# MDTester.net
KiCad netlist of a schematic drawn in EAGLE
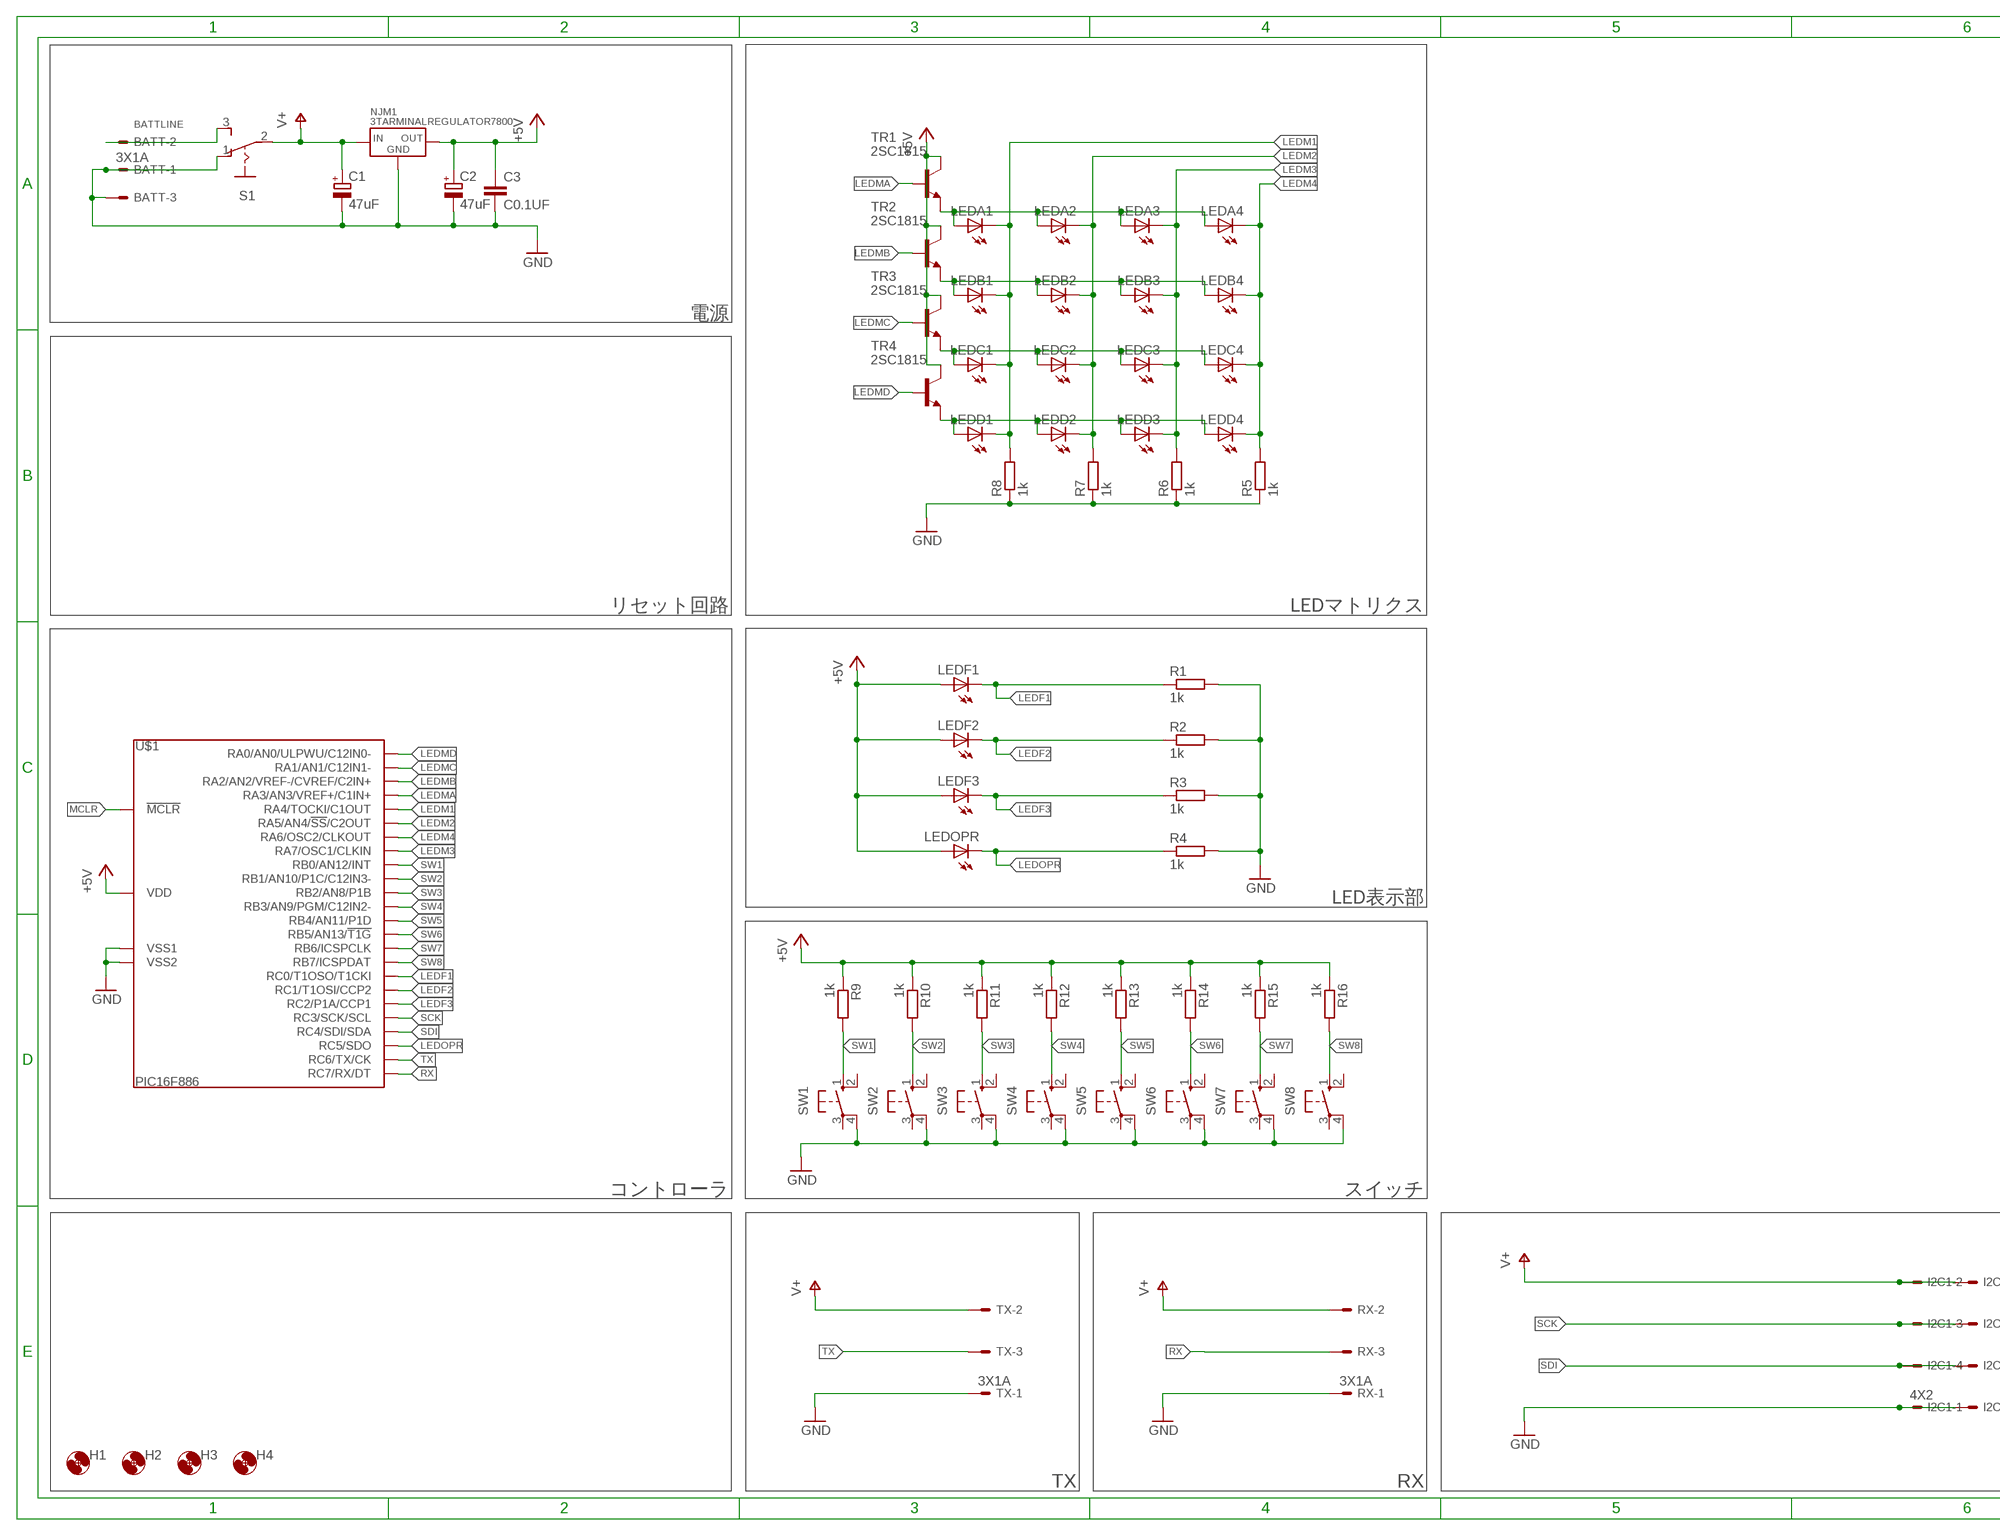
[diagram p0: schematic, sheet 1, part 1 of 2]
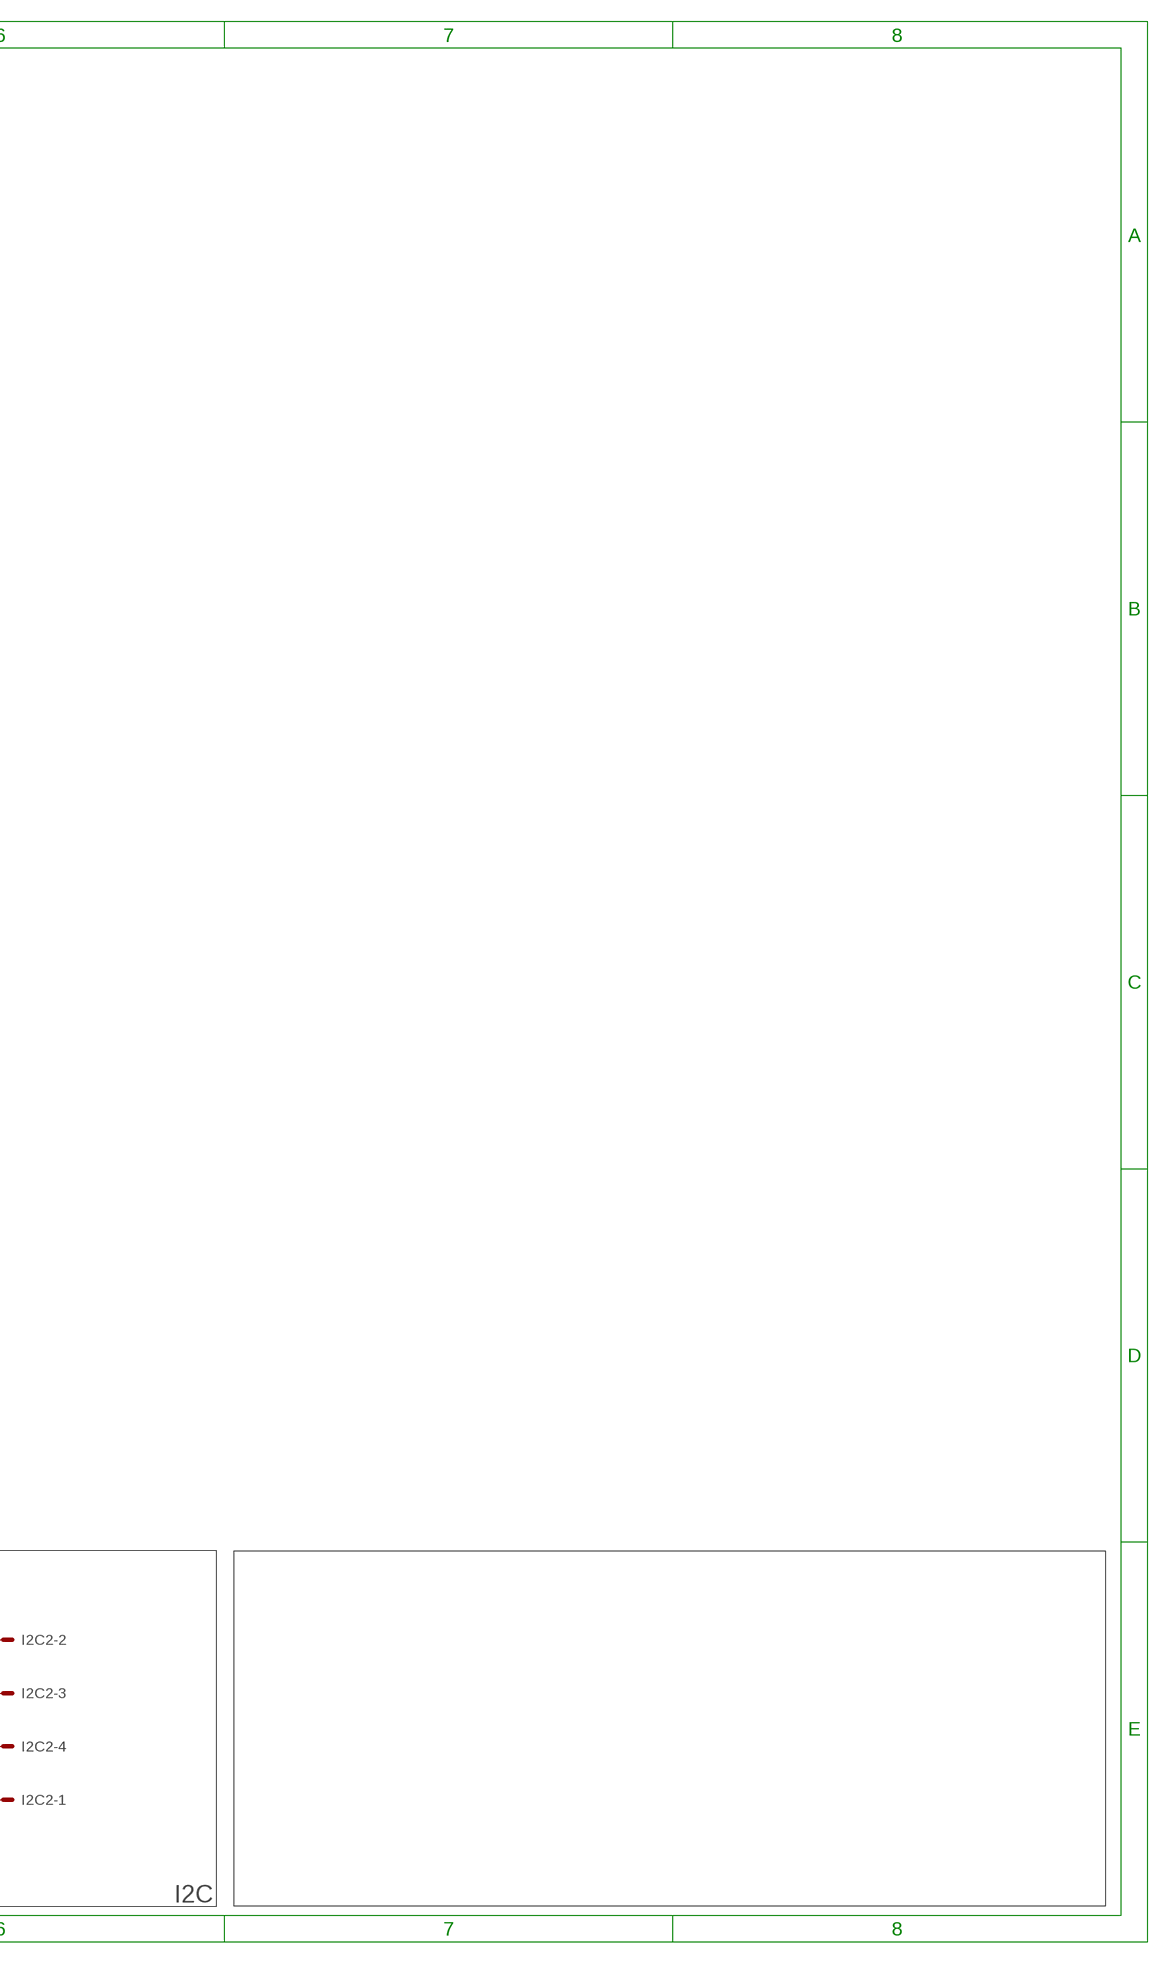
[diagram p1: schematic, sheet 1, part 2 of 2]

(export (version "E")
  (design (tool "Eeschema 10.0.6"))
  (components
    (comp (ref "BATT")
      (value "3X1A")
      (footprint "eagle-import:37203-62A3-003")
      (libsource (lib "eagle-import") (part "3X1A"))
    )
    (comp (ref "C1")
      (value "47uF")
      (footprint "eagle-import:E2-5")
      (libsource (lib "eagle-import") (part "CPOL-EU2-5MM"))
    )
    (comp (ref "C2")
      (value "47uF")
      (footprint "eagle-import:E2-5")
      (libsource (lib "eagle-import") (part "CPOL-EU2-5MM"))
    )
    (comp (ref "C3")
      (value "C0.1UF")
      (footprint "eagle-import:C0.1UF")
      (libsource (lib "eagle-import") (part "C0.1UF"))
    )
    (comp (ref "H1")
      (value "HOLE3.3M3BOLT")
      (footprint "eagle-import:HOLE3.3")
      (libsource (lib "eagle-import") (part "HOLE3.3M3BOLT"))
    )
    (comp (ref "H2")
      (value "HOLE3.3M3BOLT")
      (footprint "eagle-import:HOLE3.3")
      (libsource (lib "eagle-import") (part "HOLE3.3M3BOLT"))
    )
    (comp (ref "H3")
      (value "HOLE3.3M3BOLT")
      (footprint "eagle-import:HOLE3.3")
      (libsource (lib "eagle-import") (part "HOLE3.3M3BOLT"))
    )
    (comp (ref "H4")
      (value "HOLE3.3M3BOLT")
      (footprint "eagle-import:HOLE3.3")
      (libsource (lib "eagle-import") (part "HOLE3.3M3BOLT"))
    )
    (comp (ref "I2C")
      (value "4X2")
      (footprint "eagle-import:37208-62A3-004")
      (libsource (lib "eagle-import") (part "4X2"))
    )
    (comp (ref "LEDA1")
      (value "LED5MM")
      (footprint "eagle-import:LED5MM")
      (libsource (lib "eagle-import") (part "LED5MM"))
    )
    (comp (ref "LEDA2")
      (value "LED5MM")
      (footprint "eagle-import:LED5MM")
      (libsource (lib "eagle-import") (part "LED5MM"))
    )
    (comp (ref "LEDA3")
      (value "LED5MM")
      (footprint "eagle-import:LED5MM")
      (libsource (lib "eagle-import") (part "LED5MM"))
    )
    (comp (ref "LEDA4")
      (value "LED5MM")
      (footprint "eagle-import:LED5MM")
      (libsource (lib "eagle-import") (part "LED5MM"))
    )
    (comp (ref "LEDB1")
      (value "LED5MM")
      (footprint "eagle-import:LED5MM")
      (libsource (lib "eagle-import") (part "LED5MM"))
    )
    (comp (ref "LEDB2")
      (value "LED5MM")
      (footprint "eagle-import:LED5MM")
      (libsource (lib "eagle-import") (part "LED5MM"))
    )
    (comp (ref "LEDB3")
      (value "LED5MM")
      (footprint "eagle-import:LED5MM")
      (libsource (lib "eagle-import") (part "LED5MM"))
    )
    (comp (ref "LEDB4")
      (value "LED5MM")
      (footprint "eagle-import:LED5MM")
      (libsource (lib "eagle-import") (part "LED5MM"))
    )
    (comp (ref "LEDC1")
      (value "LED5MM")
      (footprint "eagle-import:LED5MM")
      (libsource (lib "eagle-import") (part "LED5MM"))
    )
    (comp (ref "LEDC2")
      (value "LED5MM")
      (footprint "eagle-import:LED5MM")
      (libsource (lib "eagle-import") (part "LED5MM"))
    )
    (comp (ref "LEDC3")
      (value "LED5MM")
      (footprint "eagle-import:LED5MM")
      (libsource (lib "eagle-import") (part "LED5MM"))
    )
    (comp (ref "LEDC4")
      (value "LED5MM")
      (footprint "eagle-import:LED5MM")
      (libsource (lib "eagle-import") (part "LED5MM"))
    )
    (comp (ref "LEDD1")
      (value "LED5MM")
      (footprint "eagle-import:LED5MM")
      (libsource (lib "eagle-import") (part "LED5MM"))
    )
    (comp (ref "LEDD2")
      (value "LED5MM")
      (footprint "eagle-import:LED5MM")
      (libsource (lib "eagle-import") (part "LED5MM"))
    )
    (comp (ref "LEDD3")
      (value "LED5MM")
      (footprint "eagle-import:LED5MM")
      (libsource (lib "eagle-import") (part "LED5MM"))
    )
    (comp (ref "LEDD4")
      (value "LED5MM")
      (footprint "eagle-import:LED5MM")
      (libsource (lib "eagle-import") (part "LED5MM"))
    )
    (comp (ref "LEDF1")
      (value "LED5MM")
      (footprint "eagle-import:LED5MM")
      (libsource (lib "eagle-import") (part "LED5MM"))
    )
    (comp (ref "LEDF2")
      (value "LED5MM")
      (footprint "eagle-import:LED5MM")
      (libsource (lib "eagle-import") (part "LED5MM"))
    )
    (comp (ref "LEDF3")
      (value "LED5MM")
      (footprint "eagle-import:LED5MM")
      (libsource (lib "eagle-import") (part "LED5MM"))
    )
    (comp (ref "LEDOPR")
      (value "LED5MM")
      (footprint "eagle-import:LED5MM")
      (libsource (lib "eagle-import") (part "LED5MM"))
    )
    (comp (ref "NJM1")
      (value "3TARMINALREGULATOR7800")
      (footprint "eagle-import:TO-220")
      (libsource (lib "eagle-import") (part "3TARMINALREGULATOR7800"))
    )
    (comp (ref "R1")
      (value "1k")
      (footprint "eagle-import:R3216W")
      (libsource (lib "eagle-import") (part "R-EU_R3216W"))
    )
    (comp (ref "R2")
      (value "1k")
      (footprint "eagle-import:R3216W")
      (libsource (lib "eagle-import") (part "R-EU_R3216W"))
    )
    (comp (ref "R3")
      (value "1k")
      (footprint "eagle-import:R3216W")
      (libsource (lib "eagle-import") (part "R-EU_R3216W"))
    )
    (comp (ref "R4")
      (value "1k")
      (footprint "eagle-import:R3216W")
      (libsource (lib "eagle-import") (part "R-EU_R3216W"))
    )
    (comp (ref "R5")
      (value "1k")
      (footprint "eagle-import:R3216W")
      (libsource (lib "eagle-import") (part "R-EU_R3216W"))
    )
    (comp (ref "R6")
      (value "1k")
      (footprint "eagle-import:R3216W")
      (libsource (lib "eagle-import") (part "R-EU_R3216W"))
    )
    (comp (ref "R7")
      (value "1k")
      (footprint "eagle-import:R3216W")
      (libsource (lib "eagle-import") (part "R-EU_R3216W"))
    )
    (comp (ref "R8")
      (value "1k")
      (footprint "eagle-import:R3216W")
      (libsource (lib "eagle-import") (part "R-EU_R3216W"))
    )
    (comp (ref "R9")
      (value "1k")
      (footprint "eagle-import:R3216W")
      (libsource (lib "eagle-import") (part "R-EU_R3216W"))
    )
    (comp (ref "R10")
      (value "1k")
      (footprint "eagle-import:R3216W")
      (libsource (lib "eagle-import") (part "R-EU_R3216W"))
    )
    (comp (ref "R11")
      (value "1k")
      (footprint "eagle-import:R3216W")
      (libsource (lib "eagle-import") (part "R-EU_R3216W"))
    )
    (comp (ref "R12")
      (value "1k")
      (footprint "eagle-import:R3216W")
      (libsource (lib "eagle-import") (part "R-EU_R3216W"))
    )
    (comp (ref "R13")
      (value "1k")
      (footprint "eagle-import:R3216W")
      (libsource (lib "eagle-import") (part "R-EU_R3216W"))
    )
    (comp (ref "R14")
      (value "1k")
      (footprint "eagle-import:R3216W")
      (libsource (lib "eagle-import") (part "R-EU_R3216W"))
    )
    (comp (ref "R15")
      (value "1k")
      (footprint "eagle-import:R3216W")
      (libsource (lib "eagle-import") (part "R-EU_R3216W"))
    )
    (comp (ref "R16")
      (value "1k")
      (footprint "eagle-import:R3216W")
      (libsource (lib "eagle-import") (part "R-EU_R3216W"))
    )
    (comp (ref "RX")
      (value "3X1A")
      (footprint "eagle-import:37203-62A3-003")
      (libsource (lib "eagle-import") (part "3X1A"))
    )
    (comp (ref "S1")
      (value "SLIDESW")
      (footprint "eagle-import:SLIDESW")
      (libsource (lib "eagle-import") (part "SLIDESW"))
    )
    (comp (ref "SW1")
      (value "TACTSW")
      (footprint "eagle-import:TACT")
      (libsource (lib "eagle-import") (part "TACTSW"))
    )
    (comp (ref "SW2")
      (value "TACTSW")
      (footprint "eagle-import:TACT")
      (libsource (lib "eagle-import") (part "TACTSW"))
    )
    (comp (ref "SW3")
      (value "TACTSW")
      (footprint "eagle-import:TACT")
      (libsource (lib "eagle-import") (part "TACTSW"))
    )
    (comp (ref "SW4")
      (value "TACTSW")
      (footprint "eagle-import:TACT")
      (libsource (lib "eagle-import") (part "TACTSW"))
    )
    (comp (ref "SW5")
      (value "TACTSW")
      (footprint "eagle-import:TACT")
      (libsource (lib "eagle-import") (part "TACTSW"))
    )
    (comp (ref "SW6")
      (value "TACTSW")
      (footprint "eagle-import:TACT")
      (libsource (lib "eagle-import") (part "TACTSW"))
    )
    (comp (ref "SW7")
      (value "TACTSW")
      (footprint "eagle-import:TACT")
      (libsource (lib "eagle-import") (part "TACTSW"))
    )
    (comp (ref "SW8")
      (value "TACTSW")
      (footprint "eagle-import:TACT")
      (libsource (lib "eagle-import") (part "TACTSW"))
    )
    (comp (ref "TR1")
      (value "2SC1815")
      (footprint "eagle-import:TO92-")
      (libsource (lib "eagle-import") (part "2SC1815"))
    )
    (comp (ref "TR2")
      (value "2SC1815")
      (footprint "eagle-import:TO92-")
      (libsource (lib "eagle-import") (part "2SC1815"))
    )
    (comp (ref "TR3")
      (value "2SC1815")
      (footprint "eagle-import:TO92-")
      (libsource (lib "eagle-import") (part "2SC1815"))
    )
    (comp (ref "TR4")
      (value "2SC1815")
      (footprint "eagle-import:TO92-")
      (libsource (lib "eagle-import") (part "2SC1815"))
    )
    (comp (ref "TX")
      (value "3X1A")
      (footprint "eagle-import:37203-62A3-003")
      (libsource (lib "eagle-import") (part "3X1A"))
    )
    (comp (ref "U$1")
      (value "PIC16F886")
      (footprint "eagle-import:DIL28")
      (libsource (lib "eagle-import") (part "PIC16F886"))
    )
  )
  (nets
    (net (code "1") (name "+5V") (class "Default")
      (node (ref "C2") (pin "+") (pinfunction "+_+") (pintype "passive"))
      (node (ref "C3") (pin "1") (pinfunction "1_1") (pintype "passive"))
      (node (ref "LEDF1") (pin "A") (pinfunction "A_A") (pintype "passive"))
      (node (ref "LEDF2") (pin "A") (pinfunction "A_A") (pintype "passive"))
      (node (ref "LEDF3") (pin "A") (pinfunction "A_A") (pintype "passive"))
      (node (ref "LEDOPR") (pin "A") (pinfunction "A_A") (pintype "passive"))
      (node (ref "NJM1") (pin "OUT") (pinfunction "OUT_OUT") (pintype "passive"))
      (node (ref "R10") (pin "1") (pinfunction "1_1") (pintype "passive"))
      (node (ref "R11") (pin "1") (pinfunction "1_1") (pintype "passive"))
      (node (ref "R12") (pin "1") (pinfunction "1_1") (pintype "passive"))
      (node (ref "R13") (pin "1") (pinfunction "1_1") (pintype "passive"))
      (node (ref "R14") (pin "1") (pinfunction "1_1") (pintype "passive"))
      (node (ref "R15") (pin "1") (pinfunction "1_1") (pintype "passive"))
      (node (ref "R16") (pin "1") (pinfunction "1_1") (pintype "passive"))
      (node (ref "R9") (pin "1") (pinfunction "1_1") (pintype "passive"))
      (node (ref "TR1") (pin "C") (pinfunction "C_C") (pintype "passive"))
      (node (ref "TR2") (pin "C") (pinfunction "C_C") (pintype "passive"))
      (node (ref "TR3") (pin "C") (pinfunction "C_C") (pintype "passive"))
      (node (ref "TR4") (pin "C") (pinfunction "C_C") (pintype "passive"))
      (node (ref "U$1") (pin "20") (pinfunction "VDD_20") (pintype "passive"))
    )
    (net (code "2") (name "/BATTLINE") (class "Default")
      (node (ref "BATT") (pin "1-2") (pinfunction "S_1-2") (pintype "passive"))
      (node (ref "S1") (pin "3") (pinfunction "3_3") (pintype "passive"))
    )
    (net (code "3") (name "GND") (class "Default")
      (node (ref "BATT") (pin "1-1") (pinfunction "S_1-1") (pintype "passive"))
      (node (ref "BATT") (pin "1-3") (pinfunction "S_1-3") (pintype "passive"))
      (node (ref "C1") (pin "-") (pinfunction "-_-") (pintype "passive"))
      (node (ref "C2") (pin "-") (pinfunction "-_-") (pintype "passive"))
      (node (ref "C3") (pin "2") (pinfunction "2_2") (pintype "passive"))
      (node (ref "I2C") (pin "1-1") (pinfunction "S_1-1") (pintype "passive"))
      (node (ref "I2C") (pin "2-1") (pinfunction "S_2-1") (pintype "passive"))
      (node (ref "NJM1") (pin "GND") (pinfunction "GND_GND") (pintype "passive"))
      (node (ref "R1") (pin "2") (pinfunction "2_2") (pintype "passive"))
      (node (ref "R2") (pin "2") (pinfunction "2_2") (pintype "passive"))
      (node (ref "R3") (pin "2") (pinfunction "2_2") (pintype "passive"))
      (node (ref "R4") (pin "2") (pinfunction "2_2") (pintype "passive"))
      (node (ref "R5") (pin "1") (pinfunction "1_1") (pintype "passive"))
      (node (ref "R6") (pin "1") (pinfunction "1_1") (pintype "passive"))
      (node (ref "R7") (pin "1") (pinfunction "1_1") (pintype "passive"))
      (node (ref "R8") (pin "1") (pinfunction "1_1") (pintype "passive"))
      (node (ref "RX") (pin "1-1") (pinfunction "S_1-1") (pintype "passive"))
      (node (ref "S1") (pin "1") (pinfunction "1_1") (pintype "passive"))
      (node (ref "SW1") (pin "4") (pinfunction "P1_4") (pintype "passive"))
      (node (ref "SW2") (pin "4") (pinfunction "P1_4") (pintype "passive"))
      (node (ref "SW3") (pin "4") (pinfunction "P1_4") (pintype "passive"))
      (node (ref "SW4") (pin "4") (pinfunction "P1_4") (pintype "passive"))
      (node (ref "SW5") (pin "4") (pinfunction "P1_4") (pintype "passive"))
      (node (ref "SW6") (pin "4") (pinfunction "P1_4") (pintype "passive"))
      (node (ref "SW7") (pin "4") (pinfunction "P1_4") (pintype "passive"))
      (node (ref "SW8") (pin "4") (pinfunction "P1_4") (pintype "passive"))
      (node (ref "TX") (pin "1-1") (pinfunction "S_1-1") (pintype "passive"))
      (node (ref "U$1") (pin "19") (pinfunction "VSS2_19") (pintype "passive"))
      (node (ref "U$1") (pin "8") (pinfunction "VSS1_8") (pintype "passive"))
    )
    (net (code "4") (name "LEDF1") (class "Default")
      (node (ref "LEDF1") (pin "K") (pinfunction "C_K") (pintype "passive"))
      (node (ref "R1") (pin "1") (pinfunction "1_1") (pintype "passive"))
      (node (ref "U$1") (pin "11") (pinfunction "RC0/T1OSO/T1CKI_11") (pintype "passive"))
    )
    (net (code "5") (name "LEDF2") (class "Default")
      (node (ref "LEDF2") (pin "K") (pinfunction "C_K") (pintype "passive"))
      (node (ref "R2") (pin "1") (pinfunction "1_1") (pintype "passive"))
      (node (ref "U$1") (pin "12") (pinfunction "RC1/T1OSI/CCP2_12") (pintype "passive"))
    )
    (net (code "6") (name "LEDF3") (class "Default")
      (node (ref "LEDF3") (pin "K") (pinfunction "C_K") (pintype "passive"))
      (node (ref "R3") (pin "1") (pinfunction "1_1") (pintype "passive"))
      (node (ref "U$1") (pin "13") (pinfunction "RC2/P1A/CCP1_13") (pintype "passive"))
    )
    (net (code "7") (name "LEDM1") (class "Default")
      (node (ref "LEDA1") (pin "K") (pinfunction "C_K") (pintype "passive"))
      (node (ref "LEDB1") (pin "K") (pinfunction "C_K") (pintype "passive"))
      (node (ref "LEDC1") (pin "K") (pinfunction "C_K") (pintype "passive"))
      (node (ref "LEDD1") (pin "K") (pinfunction "C_K") (pintype "passive"))
      (node (ref "R8") (pin "2") (pinfunction "2_2") (pintype "passive"))
      (node (ref "U$1") (pin "6") (pinfunction "RA4/TOCKI/C1OUT_6") (pintype "passive"))
    )
    (net (code "8") (name "LEDM2") (class "Default")
      (node (ref "LEDA2") (pin "K") (pinfunction "C_K") (pintype "passive"))
      (node (ref "LEDB2") (pin "K") (pinfunction "C_K") (pintype "passive"))
      (node (ref "LEDC2") (pin "K") (pinfunction "C_K") (pintype "passive"))
      (node (ref "LEDD2") (pin "K") (pinfunction "C_K") (pintype "passive"))
      (node (ref "R7") (pin "2") (pinfunction "2_2") (pintype "passive"))
      (node (ref "U$1") (pin "7") (pinfunction "RA5/AN4/~{SS}/C2OUT_7") (pintype "passive"))
    )
    (net (code "9") (name "LEDM3") (class "Default")
      (node (ref "LEDA3") (pin "K") (pinfunction "C_K") (pintype "passive"))
      (node (ref "LEDB3") (pin "K") (pinfunction "C_K") (pintype "passive"))
      (node (ref "LEDC3") (pin "K") (pinfunction "C_K") (pintype "passive"))
      (node (ref "LEDD3") (pin "K") (pinfunction "C_K") (pintype "passive"))
      (node (ref "R6") (pin "2") (pinfunction "2_2") (pintype "passive"))
      (node (ref "U$1") (pin "9") (pinfunction "RA7/OSC1/CLKIN_9") (pintype "passive"))
    )
    (net (code "10") (name "LEDM4") (class "Default")
      (node (ref "LEDA4") (pin "K") (pinfunction "C_K") (pintype "passive"))
      (node (ref "LEDB4") (pin "K") (pinfunction "C_K") (pintype "passive"))
      (node (ref "LEDC4") (pin "K") (pinfunction "C_K") (pintype "passive"))
      (node (ref "LEDD4") (pin "K") (pinfunction "C_K") (pintype "passive"))
      (node (ref "R5") (pin "2") (pinfunction "2_2") (pintype "passive"))
      (node (ref "U$1") (pin "10") (pinfunction "RA6/OSC2/CLKOUT_10") (pintype "passive"))
    )
    (net (code "11") (name "LEDMA") (class "Default")
      (node (ref "TR1") (pin "B") (pinfunction "B_B") (pintype "passive"))
      (node (ref "U$1") (pin "5") (pinfunction "RA3/AN3/VREF+/C1IN+_5") (pintype "passive"))
    )
    (net (code "12") (name "LEDMB") (class "Default")
      (node (ref "TR2") (pin "B") (pinfunction "B_B") (pintype "passive"))
      (node (ref "U$1") (pin "4") (pinfunction "RA2/AN2/VREF-/CVREF/C2IN+_4") (pintype "passive"))
    )
    (net (code "13") (name "LEDMC") (class "Default")
      (node (ref "TR3") (pin "B") (pinfunction "B_B") (pintype "passive"))
      (node (ref "U$1") (pin "3") (pinfunction "RA1/AN1/C12IN1-_3") (pintype "passive"))
    )
    (net (code "14") (name "LEDMD") (class "Default")
      (node (ref "TR4") (pin "B") (pinfunction "B_B") (pintype "passive"))
      (node (ref "U$1") (pin "2") (pinfunction "RA0/AN0/ULPWU/C12IN0-_2") (pintype "passive"))
    )
    (net (code "15") (name "LEDOPR") (class "Default")
      (node (ref "LEDOPR") (pin "K") (pinfunction "C_K") (pintype "passive"))
      (node (ref "R4") (pin "1") (pinfunction "1_1") (pintype "passive"))
      (node (ref "U$1") (pin "16") (pinfunction "RC5/SDO_16") (pintype "passive"))
    )
    (net (code "16") (name "MCLR") (class "Default")
      (node (ref "U$1") (pin "1") (pinfunction "~{MCLR}_1") (pintype "passive"))
    )
    (net (code "17") (name "Net-(LEDA1-PadA)") (class "Default")
      (node (ref "LEDA1") (pin "A") (pinfunction "A_A") (pintype "passive"))
      (node (ref "LEDA2") (pin "A") (pinfunction "A_A") (pintype "passive"))
      (node (ref "LEDA3") (pin "A") (pinfunction "A_A") (pintype "passive"))
      (node (ref "LEDA4") (pin "A") (pinfunction "A_A") (pintype "passive"))
      (node (ref "TR1") (pin "E") (pinfunction "E_E") (pintype "passive"))
    )
    (net (code "18") (name "Net-(LEDB1-PadA)") (class "Default")
      (node (ref "LEDB1") (pin "A") (pinfunction "A_A") (pintype "passive"))
      (node (ref "LEDB2") (pin "A") (pinfunction "A_A") (pintype "passive"))
      (node (ref "LEDB3") (pin "A") (pinfunction "A_A") (pintype "passive"))
      (node (ref "LEDB4") (pin "A") (pinfunction "A_A") (pintype "passive"))
      (node (ref "TR2") (pin "E") (pinfunction "E_E") (pintype "passive"))
    )
    (net (code "19") (name "Net-(LEDC1-PadA)") (class "Default")
      (node (ref "LEDC1") (pin "A") (pinfunction "A_A") (pintype "passive"))
      (node (ref "LEDC2") (pin "A") (pinfunction "A_A") (pintype "passive"))
      (node (ref "LEDC3") (pin "A") (pinfunction "A_A") (pintype "passive"))
      (node (ref "LEDC4") (pin "A") (pinfunction "A_A") (pintype "passive"))
      (node (ref "TR3") (pin "E") (pinfunction "E_E") (pintype "passive"))
    )
    (net (code "20") (name "Net-(LEDD1-PadA)") (class "Default")
      (node (ref "LEDD1") (pin "A") (pinfunction "A_A") (pintype "passive"))
      (node (ref "LEDD2") (pin "A") (pinfunction "A_A") (pintype "passive"))
      (node (ref "LEDD3") (pin "A") (pinfunction "A_A") (pintype "passive"))
      (node (ref "LEDD4") (pin "A") (pinfunction "A_A") (pintype "passive"))
      (node (ref "TR4") (pin "E") (pinfunction "E_E") (pintype "passive"))
    )
    (net (code "21") (name "RX") (class "Default")
      (node (ref "RX") (pin "1-3") (pinfunction "S_1-3") (pintype "passive"))
      (node (ref "U$1") (pin "18") (pinfunction "RC7/RX/DT_18") (pintype "passive"))
    )
    (net (code "22") (name "SCK") (class "Default")
      (node (ref "I2C") (pin "1-3") (pinfunction "S_1-3") (pintype "passive"))
      (node (ref "I2C") (pin "2-3") (pinfunction "S_2-3") (pintype "passive"))
      (node (ref "U$1") (pin "14") (pinfunction "RC3/SCK/SCL_14") (pintype "passive"))
    )
    (net (code "23") (name "SDI") (class "Default")
      (node (ref "I2C") (pin "1-4") (pinfunction "S_1-4") (pintype "passive"))
      (node (ref "I2C") (pin "2-4") (pinfunction "S_2-4") (pintype "passive"))
      (node (ref "U$1") (pin "15") (pinfunction "RC4/SDI/SDA_15") (pintype "passive"))
    )
    (net (code "24") (name "SW1") (class "Default")
      (node (ref "R9") (pin "2") (pinfunction "2_2") (pintype "passive"))
      (node (ref "SW1") (pin "1") (pinfunction "S_1") (pintype "passive"))
      (node (ref "U$1") (pin "21") (pinfunction "RB0/AN12/INT_21") (pintype "passive"))
    )
    (net (code "25") (name "SW2") (class "Default")
      (node (ref "R10") (pin "2") (pinfunction "2_2") (pintype "passive"))
      (node (ref "SW2") (pin "1") (pinfunction "S_1") (pintype "passive"))
      (node (ref "U$1") (pin "22") (pinfunction "RB1/AN10/P1C/C12IN3-_22") (pintype "passive"))
    )
    (net (code "26") (name "SW3") (class "Default")
      (node (ref "R11") (pin "2") (pinfunction "2_2") (pintype "passive"))
      (node (ref "SW3") (pin "1") (pinfunction "S_1") (pintype "passive"))
      (node (ref "U$1") (pin "23") (pinfunction "RB2/AN8/P1B_23") (pintype "passive"))
    )
    (net (code "27") (name "SW4") (class "Default")
      (node (ref "R12") (pin "2") (pinfunction "2_2") (pintype "passive"))
      (node (ref "SW4") (pin "1") (pinfunction "S_1") (pintype "passive"))
      (node (ref "U$1") (pin "24") (pinfunction "RB3/AN9/PGM/C12IN2-_24") (pintype "passive"))
    )
    (net (code "28") (name "SW5") (class "Default")
      (node (ref "R13") (pin "2") (pinfunction "2_2") (pintype "passive"))
      (node (ref "SW5") (pin "1") (pinfunction "S_1") (pintype "passive"))
      (node (ref "U$1") (pin "25") (pinfunction "RB4/AN11/P1D_25") (pintype "passive"))
    )
    (net (code "29") (name "SW6") (class "Default")
      (node (ref "R14") (pin "2") (pinfunction "2_2") (pintype "passive"))
      (node (ref "SW6") (pin "1") (pinfunction "S_1") (pintype "passive"))
      (node (ref "U$1") (pin "26") (pinfunction "RB5/AN13/~{T1G}_26") (pintype "passive"))
    )
    (net (code "30") (name "SW7") (class "Default")
      (node (ref "R15") (pin "2") (pinfunction "2_2") (pintype "passive"))
      (node (ref "SW7") (pin "1") (pinfunction "S_1") (pintype "passive"))
      (node (ref "U$1") (pin "27") (pinfunction "RB6/ICSPCLK_27") (pintype "passive"))
    )
    (net (code "31") (name "SW8") (class "Default")
      (node (ref "R16") (pin "2") (pinfunction "2_2") (pintype "passive"))
      (node (ref "SW8") (pin "1") (pinfunction "S_1") (pintype "passive"))
      (node (ref "U$1") (pin "28") (pinfunction "RB7/ICSPDAT_28") (pintype "passive"))
    )
    (net (code "32") (name "TX") (class "Default")
      (node (ref "TX") (pin "1-3") (pinfunction "S_1-3") (pintype "passive"))
      (node (ref "U$1") (pin "17") (pinfunction "RC6/TX/CK_17") (pintype "passive"))
    )
    (net (code "33") (name "V+") (class "Default")
      (node (ref "C1") (pin "+") (pinfunction "+_+") (pintype "passive"))
      (node (ref "I2C") (pin "1-2") (pinfunction "S_1-2") (pintype "passive"))
      (node (ref "I2C") (pin "2-2") (pinfunction "S_2-2") (pintype "passive"))
      (node (ref "NJM1") (pin "IN") (pinfunction "IN_IN") (pintype "passive"))
      (node (ref "RX") (pin "1-2") (pinfunction "S_1-2") (pintype "passive"))
      (node (ref "S1") (pin "2") (pinfunction "2_2") (pintype "passive"))
      (node (ref "TX") (pin "1-2") (pinfunction "S_1-2") (pintype "passive"))
    )
    (net (code "34") (name "unconnected-(SW1-P-Pad3)") (class "Default")
      (node (ref "SW1") (pin "3") (pinfunction "P_3") (pintype "passive"))
    )
    (net (code "35") (name "unconnected-(SW1-S1-Pad2)") (class "Default")
      (node (ref "SW1") (pin "2") (pinfunction "S1_2") (pintype "passive"))
    )
    (net (code "36") (name "unconnected-(SW2-P-Pad3)") (class "Default")
      (node (ref "SW2") (pin "3") (pinfunction "P_3") (pintype "passive"))
    )
    (net (code "37") (name "unconnected-(SW2-S1-Pad2)") (class "Default")
      (node (ref "SW2") (pin "2") (pinfunction "S1_2") (pintype "passive"))
    )
    (net (code "38") (name "unconnected-(SW3-P-Pad3)") (class "Default")
      (node (ref "SW3") (pin "3") (pinfunction "P_3") (pintype "passive"))
    )
    (net (code "39") (name "unconnected-(SW3-S1-Pad2)") (class "Default")
      (node (ref "SW3") (pin "2") (pinfunction "S1_2") (pintype "passive"))
    )
    (net (code "40") (name "unconnected-(SW4-P-Pad3)") (class "Default")
      (node (ref "SW4") (pin "3") (pinfunction "P_3") (pintype "passive"))
    )
    (net (code "41") (name "unconnected-(SW4-S1-Pad2)") (class "Default")
      (node (ref "SW4") (pin "2") (pinfunction "S1_2") (pintype "passive"))
    )
    (net (code "42") (name "unconnected-(SW5-P-Pad3)") (class "Default")
      (node (ref "SW5") (pin "3") (pinfunction "P_3") (pintype "passive"))
    )
    (net (code "43") (name "unconnected-(SW5-S1-Pad2)") (class "Default")
      (node (ref "SW5") (pin "2") (pinfunction "S1_2") (pintype "passive"))
    )
    (net (code "44") (name "unconnected-(SW6-P-Pad3)") (class "Default")
      (node (ref "SW6") (pin "3") (pinfunction "P_3") (pintype "passive"))
    )
    (net (code "45") (name "unconnected-(SW6-S1-Pad2)") (class "Default")
      (node (ref "SW6") (pin "2") (pinfunction "S1_2") (pintype "passive"))
    )
    (net (code "46") (name "unconnected-(SW7-P-Pad3)") (class "Default")
      (node (ref "SW7") (pin "3") (pinfunction "P_3") (pintype "passive"))
    )
    (net (code "47") (name "unconnected-(SW7-S1-Pad2)") (class "Default")
      (node (ref "SW7") (pin "2") (pinfunction "S1_2") (pintype "passive"))
    )
    (net (code "48") (name "unconnected-(SW8-P-Pad3)") (class "Default")
      (node (ref "SW8") (pin "3") (pinfunction "P_3") (pintype "passive"))
    )
    (net (code "49") (name "unconnected-(SW8-S1-Pad2)") (class "Default")
      (node (ref "SW8") (pin "2") (pinfunction "S1_2") (pintype "passive"))
    )
  )
)
